# AlimTeleinfoMySensors.net
KiCad netlist of a schematic drawn in EAGLE
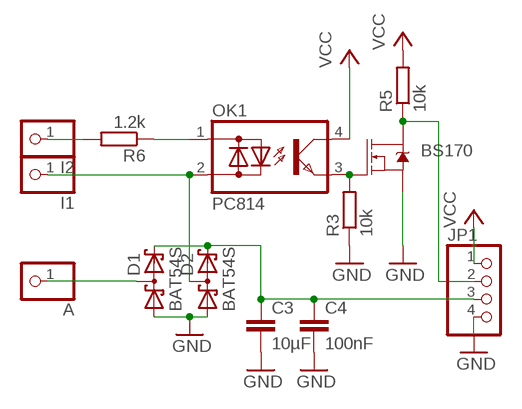
[diagram p0: schematic, sheet 1]

(export (version "E")
  (design (tool "Eeschema 10.0.6"))
  (components
    (comp (ref "A")
      (value "PINHD-1X1")
      (footprint "eagle-import:1X01")
      (libsource (lib "eagle-import") (part "PINHD-1X1"))
    )
    (comp (ref "BS170")
      (value "MOSFET-NCH-BSS138")
      (footprint "eagle-import:SOT23-3")
      (libsource (lib "eagle-import") (part "MOSFET-NCH-BSS138"))
    )
    (comp (ref "C3")
      (value "10µF")
      (footprint "eagle-import:C1210")
      (libsource (lib "eagle-import") (part "C-EUC1210"))
    )
    (comp (ref "C4")
      (value "100nF")
      (footprint "eagle-import:C1206")
      (libsource (lib "eagle-import") (part "C-EUC1206"))
    )
    (comp (ref "D1")
      (value "BAT54S")
      (footprint "eagle-import:SOT23")
      (libsource (lib "eagle-import") (part "BAT54S"))
    )
    (comp (ref "D2")
      (value "BAT54S")
      (footprint "eagle-import:SOT23")
      (libsource (lib "eagle-import") (part "BAT54S"))
    )
    (comp (ref "I1")
      (value "PINHD-1X1")
      (footprint "eagle-import:1X01")
      (libsource (lib "eagle-import") (part "PINHD-1X1"))
    )
    (comp (ref "I2")
      (value "PINHD-1X1")
      (footprint "eagle-import:1X01")
      (libsource (lib "eagle-import") (part "PINHD-1X1"))
    )
    (comp (ref "JP1")
      (value "PINHD-1X4")
      (footprint "eagle-import:1X04")
      (libsource (lib "eagle-import") (part "PINHD-1X4"))
    )
    (comp (ref "OK1")
      (value "PC814")
      (footprint "eagle-import:DIL04")
      (libsource (lib "eagle-import") (part "PC814"))
    )
    (comp (ref "R3")
      (value "10k")
      (footprint "eagle-import:M1206")
      (libsource (lib "eagle-import") (part "R-EU_M1206"))
    )
    (comp (ref "R5")
      (value "10k")
      (footprint "eagle-import:M1206")
      (libsource (lib "eagle-import") (part "R-EU_M1206"))
    )
    (comp (ref "R6")
      (value "1.2k")
      (footprint "eagle-import:M1206")
      (libsource (lib "eagle-import") (part "R-EU_M1206"))
    )
  )
  (nets
    (net (code "1") (name "GND") (class "Default")
      (node (ref "BS170") (pin "2") (pinfunction "S_2") (pintype "bidirectional"))
      (node (ref "C3") (pin "2") (pinfunction "2_2") (pintype "passive"))
      (node (ref "C4") (pin "2") (pinfunction "2_2") (pintype "passive"))
      (node (ref "D1") (pin "1") (pinfunction "A1_1") (pintype "passive"))
      (node (ref "D2") (pin "1") (pinfunction "A1_1") (pintype "passive"))
      (node (ref "JP1") (pin "4") (pinfunction "4_4") (pintype "passive"))
      (node (ref "R3") (pin "1") (pinfunction "1_1") (pintype "passive"))
    )
    (net (code "2") (name "Net-(BS170-D)") (class "Default")
      (node (ref "BS170") (pin "3") (pinfunction "D_3") (pintype "bidirectional"))
      (node (ref "JP1") (pin "2") (pinfunction "2_2") (pintype "passive"))
      (node (ref "R5") (pin "1") (pinfunction "1_1") (pintype "passive"))
    )
    (net (code "3") (name "Net-(BS170-G)") (class "Default")
      (node (ref "BS170") (pin "1") (pinfunction "G_1") (pintype "bidirectional"))
      (node (ref "OK1") (pin "3") (pinfunction "E_3") (pintype "passive"))
      (node (ref "R3") (pin "2") (pinfunction "2_2") (pintype "passive"))
    )
    (net (code "4") (name "Net-(D1-C1A2)") (class "Default")
      (node (ref "A") (pin "1") (pinfunction "1_1") (pintype "passive"))
      (node (ref "D1") (pin "3") (pinfunction "C1A2_3") (pintype "passive"))
    )
    (net (code "5") (name "Net-(D1-C2)") (class "Default")
      (node (ref "C3") (pin "1") (pinfunction "1_1") (pintype "passive"))
      (node (ref "C4") (pin "1") (pinfunction "1_1") (pintype "passive"))
      (node (ref "D1") (pin "2") (pinfunction "C2_2") (pintype "passive"))
      (node (ref "D2") (pin "2") (pinfunction "C2_2") (pintype "passive"))
      (node (ref "JP1") (pin "3") (pinfunction "3_3") (pintype "passive"))
    )
    (net (code "6") (name "Net-(D2-C1A2)") (class "Default")
      (node (ref "D2") (pin "3") (pinfunction "C1A2_3") (pintype "passive"))
      (node (ref "I1") (pin "1") (pinfunction "1_1") (pintype "passive"))
      (node (ref "OK1") (pin "2") (pinfunction "AC2_2") (pintype "passive"))
    )
    (net (code "7") (name "Net-(I2-Pad1)") (class "Default")
      (node (ref "I2") (pin "1") (pinfunction "1_1") (pintype "passive"))
      (node (ref "R6") (pin "2") (pinfunction "2_2") (pintype "passive"))
    )
    (net (code "8") (name "Net-(OK1-AC1)") (class "Default")
      (node (ref "OK1") (pin "1") (pinfunction "AC1_1") (pintype "passive"))
      (node (ref "R6") (pin "1") (pinfunction "1_1") (pintype "passive"))
    )
    (net (code "9") (name "VCC") (class "Default")
      (node (ref "JP1") (pin "1") (pinfunction "1_1") (pintype "passive"))
      (node (ref "OK1") (pin "4") (pinfunction "C_4") (pintype "passive"))
      (node (ref "R5") (pin "2") (pinfunction "2_2") (pintype "passive"))
    )
  )
)
